# DIO-BNC_Supply.net
KiCad netlist of a schematic drawn in Altium Designer
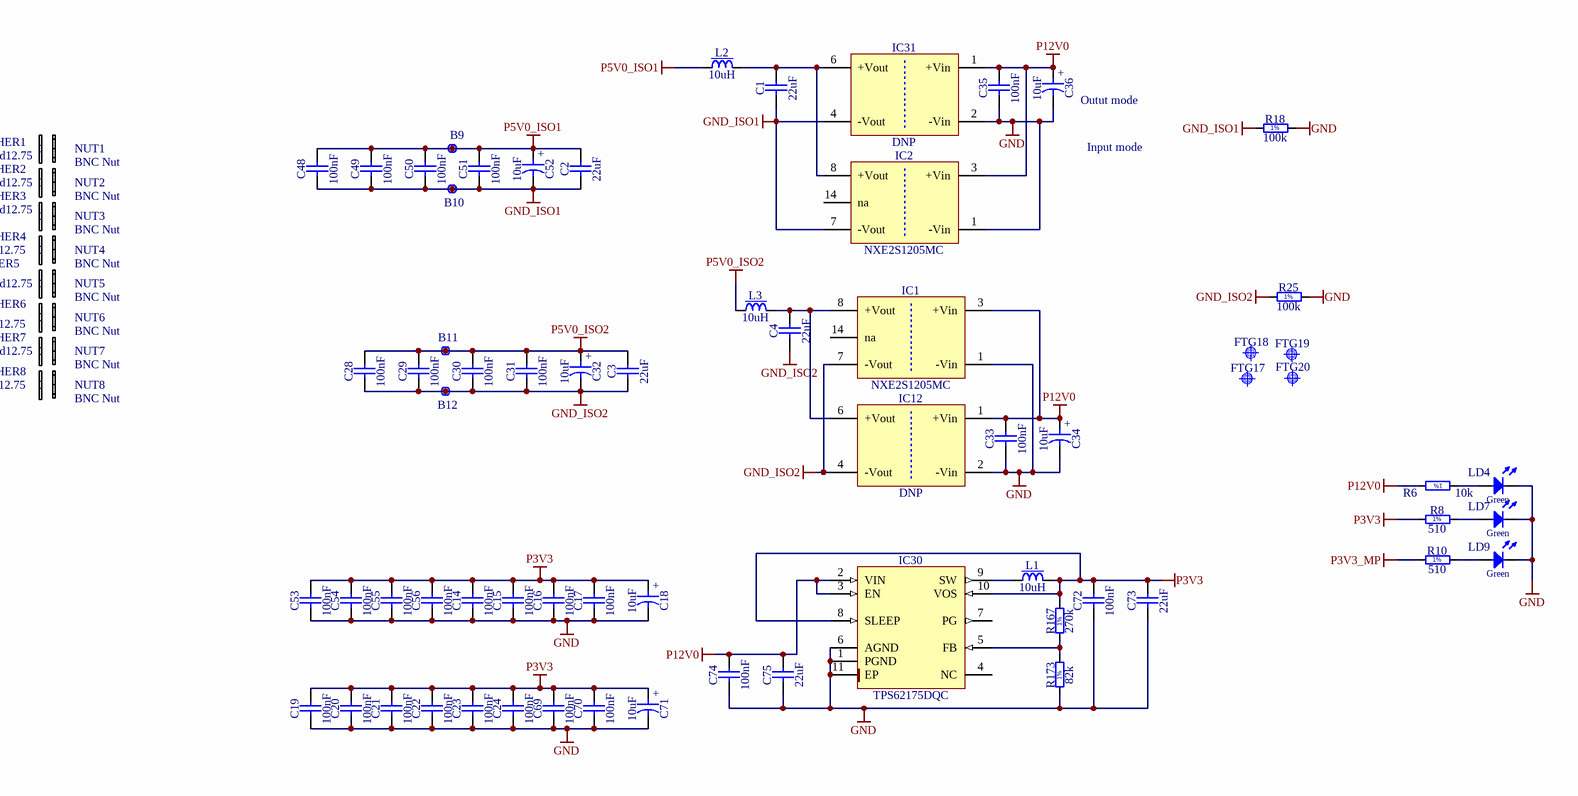
[diagram p0: DIO-BNC_Supply.SchDoc]

(export (version "E")
  (design (tool "Eeschema 10.0.6"))
  (components
    (comp (ref "B9")
      (value "Plated Hole")
      (footprint "c130h60")
      (description "Single Terminal Socket")
      (fields (field (name "PART NUMBER") "PLATED_HOLE0.6_PAD1.3") (field (name "AUTHOR") "CERN DEM MR"))
      (libsource (lib "Eletro-mechanical") (part "Single Terminal Socket"))
    )
    (comp (ref "B10")
      (value "Plated Hole")
      (footprint "c130h60")
      (description "Single Terminal Socket")
      (fields (field (name "PART NUMBER") "PLATED_HOLE0.6_PAD1.3") (field (name "AUTHOR") "CERN DEM MR"))
      (libsource (lib "Eletro-mechanical") (part "Single Terminal Socket"))
    )
    (comp (ref "B11")
      (value "Plated Hole")
      (footprint "c130h60")
      (description "Single Terminal Socket")
      (fields (field (name "PART NUMBER") "PLATED_HOLE0.6_PAD1.3") (field (name "AUTHOR") "CERN DEM MR"))
      (libsource (lib "Eletro-mechanical") (part "Single Terminal Socket"))
    )
    (comp (ref "B12")
      (value "Plated Hole")
      (footprint "c130h60")
      (description "Single Terminal Socket")
      (fields (field (name "PART NUMBER") "PLATED_HOLE0.6_PAD1.3") (field (name "AUTHOR") "CERN DEM MR"))
      (libsource (lib "Eletro-mechanical") (part "Single Terminal Socket"))
    )
    (comp (ref "C1")
      (value "22uF")
      (footprint "CAPC2012X135N")
      (description "Non-polarised capacitor")
      (fields
        (field (name "PART NUMBER") "CC0805_22UF_16V_10%_X5R")
        (field (name "VOLTAGE") "16V")
        (field (name "AUTHOR") "CERN DEM JLC")
      )
      (libsource (lib "Capacitors") (part "Capacitor - non polarized"))
    )
    (comp (ref "C2")
      (value "22uF")
      (footprint "CAPC2012X135N")
      (description "Non-polarised capacitor")
      (fields
        (field (name "PART NUMBER") "CC0805_22UF_16V_10%_X5R")
        (field (name "VOLTAGE") "16V")
        (field (name "AUTHOR") "CERN DEM JLC")
      )
      (libsource (lib "Capacitors") (part "Capacitor - non polarized"))
    )
    (comp (ref "C3")
      (value "22uF")
      (footprint "CAPC2012X135N")
      (description "Non-polarised capacitor")
      (fields
        (field (name "PART NUMBER") "CC0805_22UF_16V_10%_X5R")
        (field (name "VOLTAGE") "16V")
        (field (name "AUTHOR") "CERN DEM JLC")
      )
      (libsource (lib "Capacitors") (part "Capacitor - non polarized"))
    )
    (comp (ref "C4")
      (value "22uF")
      (footprint "CAPC2012X135N")
      (description "Non-polarised capacitor")
      (fields
        (field (name "PART NUMBER") "CC0805_22UF_16V_10%_X5R")
        (field (name "VOLTAGE") "16V")
        (field (name "AUTHOR") "CERN DEM JLC")
      )
      (libsource (lib "Capacitors") (part "Capacitor - non polarized"))
    )
    (comp (ref "C14")
      (value "100nF")
      (footprint "CAPC1005X55N")
      (description "Non-polarised capacitor")
      (fields
        (field (name "PART NUMBER") "CC0402_100NF_16V_10%_X5R")
        (field (name "VOLTAGE") "16V")
        (field (name "AUTHOR") "CERN DEM JLC")
      )
      (libsource (lib "Capacitors") (part "Capacitor - non polarized"))
    )
    (comp (ref "C15")
      (value "100nF")
      (footprint "CAPC1005X55N")
      (description "Non-polarised capacitor")
      (fields
        (field (name "PART NUMBER") "CC0402_100NF_16V_10%_X5R")
        (field (name "VOLTAGE") "16V")
        (field (name "AUTHOR") "CERN DEM JLC")
      )
      (libsource (lib "Capacitors") (part "Capacitor - non polarized"))
    )
    (comp (ref "C16")
      (value "100nF")
      (footprint "CAPC1005X55N")
      (description "Non-polarised capacitor")
      (fields
        (field (name "PART NUMBER") "CC0402_100NF_16V_10%_X5R")
        (field (name "VOLTAGE") "16V")
        (field (name "AUTHOR") "CERN DEM JLC")
      )
      (libsource (lib "Capacitors") (part "Capacitor - non polarized"))
    )
    (comp (ref "C17")
      (value "100nF")
      (footprint "CAPC1005X55N")
      (description "Non-polarised capacitor")
      (fields
        (field (name "PART NUMBER") "CC0402_100NF_16V_10%_X5R")
        (field (name "VOLTAGE") "16V")
        (field (name "AUTHOR") "CERN DEM JLC")
      )
      (libsource (lib "Capacitors") (part "Capacitor - non polarized"))
    )
    (comp (ref "C18")
      (value "10uF")
      (footprint "CAPAE430X540N")
      (description "Polarised capacitor")
      (fields
        (field (name "PART NUMBER") "CAE430-540_10UF_16V_20%")
        (field (name "VOLTAGE") "16V")
        (field (name "AUTHOR") "CERN DEM JLC")
      )
      (libsource (lib "Capacitors") (part "Capacitor - polarized"))
    )
    (comp (ref "C19")
      (value "100nF")
      (footprint "CAPC1005X55N")
      (description "Non-polarised capacitor")
      (fields
        (field (name "PART NUMBER") "CC0402_100NF_16V_10%_X5R")
        (field (name "VOLTAGE") "16V")
        (field (name "AUTHOR") "CERN DEM JLC")
      )
      (libsource (lib "Capacitors") (part "Capacitor - non polarized"))
    )
    (comp (ref "C20")
      (value "100nF")
      (footprint "CAPC1005X55N")
      (description "Non-polarised capacitor")
      (fields
        (field (name "PART NUMBER") "CC0402_100NF_16V_10%_X5R")
        (field (name "VOLTAGE") "16V")
        (field (name "AUTHOR") "CERN DEM JLC")
      )
      (libsource (lib "Capacitors") (part "Capacitor - non polarized"))
    )
    (comp (ref "C21")
      (value "100nF")
      (footprint "CAPC1005X55N")
      (description "Non-polarised capacitor")
      (fields
        (field (name "PART NUMBER") "CC0402_100NF_16V_10%_X5R")
        (field (name "VOLTAGE") "16V")
        (field (name "AUTHOR") "CERN DEM JLC")
      )
      (libsource (lib "Capacitors") (part "Capacitor - non polarized"))
    )
    (comp (ref "C22")
      (value "100nF")
      (footprint "CAPC1005X55N")
      (description "Non-polarised capacitor")
      (fields
        (field (name "PART NUMBER") "CC0402_100NF_16V_10%_X5R")
        (field (name "VOLTAGE") "16V")
        (field (name "AUTHOR") "CERN DEM JLC")
      )
      (libsource (lib "Capacitors") (part "Capacitor - non polarized"))
    )
    (comp (ref "C23")
      (value "100nF")
      (footprint "CAPC1005X55N")
      (description "Non-polarised capacitor")
      (fields
        (field (name "PART NUMBER") "CC0402_100NF_16V_10%_X5R")
        (field (name "VOLTAGE") "16V")
        (field (name "AUTHOR") "CERN DEM JLC")
      )
      (libsource (lib "Capacitors") (part "Capacitor - non polarized"))
    )
    (comp (ref "C24")
      (value "100nF")
      (footprint "CAPC1005X55N")
      (description "Non-polarised capacitor")
      (fields
        (field (name "PART NUMBER") "CC0402_100NF_16V_10%_X5R")
        (field (name "VOLTAGE") "16V")
        (field (name "AUTHOR") "CERN DEM JLC")
      )
      (libsource (lib "Capacitors") (part "Capacitor - non polarized"))
    )
    (comp (ref "C28")
      (value "100nF")
      (footprint "CAPC1005X55N")
      (description "Non-polarised capacitor")
      (fields
        (field (name "PART NUMBER") "CC0402_100NF_16V_10%_X5R")
        (field (name "VOLTAGE") "16V")
        (field (name "AUTHOR") "CERN DEM JLC")
      )
      (libsource (lib "Capacitors") (part "Capacitor - non polarized"))
    )
    (comp (ref "C29")
      (value "100nF")
      (footprint "CAPC1005X55N")
      (description "Non-polarised capacitor")
      (fields
        (field (name "PART NUMBER") "CC0402_100NF_16V_10%_X5R")
        (field (name "VOLTAGE") "16V")
        (field (name "AUTHOR") "CERN DEM JLC")
      )
      (libsource (lib "Capacitors") (part "Capacitor - non polarized"))
    )
    (comp (ref "C30")
      (value "100nF")
      (footprint "CAPC1005X55N")
      (description "Non-polarised capacitor")
      (fields
        (field (name "PART NUMBER") "CC0402_100NF_16V_10%_X5R")
        (field (name "VOLTAGE") "16V")
        (field (name "AUTHOR") "CERN DEM JLC")
      )
      (libsource (lib "Capacitors") (part "Capacitor - non polarized"))
    )
    (comp (ref "C31")
      (value "100nF")
      (footprint "CAPC1005X55N")
      (description "Non-polarised capacitor")
      (fields
        (field (name "PART NUMBER") "CC0402_100NF_16V_10%_X5R")
        (field (name "VOLTAGE") "16V")
        (field (name "AUTHOR") "CERN DEM JLC")
      )
      (libsource (lib "Capacitors") (part "Capacitor - non polarized"))
    )
    (comp (ref "C32")
      (value "10uF")
      (footprint "CAPAE430X540N")
      (description "Polarised capacitor")
      (fields
        (field (name "PART NUMBER") "CAE430-540_10UF_16V_20%")
        (field (name "VOLTAGE") "16V")
        (field (name "AUTHOR") "CERN DEM JLC")
      )
      (libsource (lib "Capacitors") (part "Capacitor - polarized"))
    )
    (comp (ref "C33")
      (value "100nF")
      (footprint "CAPC1005X55N")
      (description "Non-polarised capacitor")
      (fields
        (field (name "PART NUMBER") "CC0402_100NF_16V_10%_X5R")
        (field (name "VOLTAGE") "16V")
        (field (name "AUTHOR") "CERN DEM JLC")
      )
      (libsource (lib "Capacitors") (part "Capacitor - non polarized"))
    )
    (comp (ref "C34")
      (value "10uF")
      (footprint "CAPAE430X540N")
      (description "Polarised capacitor")
      (fields
        (field (name "PART NUMBER") "CAE430-540_10UF_16V_20%")
        (field (name "VOLTAGE") "16V")
        (field (name "AUTHOR") "CERN DEM JLC")
      )
      (libsource (lib "Capacitors") (part "Capacitor - polarized"))
    )
    (comp (ref "C35")
      (value "100nF")
      (footprint "CAPC1005X55N")
      (description "Non-polarised capacitor")
      (fields
        (field (name "PART NUMBER") "CC0402_100NF_16V_10%_X5R")
        (field (name "VOLTAGE") "16V")
        (field (name "AUTHOR") "CERN DEM JLC")
      )
      (libsource (lib "Capacitors") (part "Capacitor - non polarized"))
    )
    (comp (ref "C36")
      (value "10uF")
      (footprint "CAPAE430X540N")
      (description "Polarised capacitor")
      (fields
        (field (name "PART NUMBER") "CAE430-540_10UF_16V_20%")
        (field (name "VOLTAGE") "16V")
        (field (name "AUTHOR") "CERN DEM JLC")
      )
      (libsource (lib "Capacitors") (part "Capacitor - polarized"))
    )
    (comp (ref "C48")
      (value "100nF")
      (footprint "CAPC1005X55N")
      (description "Non-polarised capacitor")
      (fields
        (field (name "PART NUMBER") "CC0402_100NF_16V_10%_X5R")
        (field (name "VOLTAGE") "16V")
        (field (name "AUTHOR") "CERN DEM JLC")
      )
      (libsource (lib "Capacitors") (part "Capacitor - non polarized"))
    )
    (comp (ref "C49")
      (value "100nF")
      (footprint "CAPC1005X55N")
      (description "Non-polarised capacitor")
      (fields
        (field (name "PART NUMBER") "CC0402_100NF_16V_10%_X5R")
        (field (name "VOLTAGE") "16V")
        (field (name "AUTHOR") "CERN DEM JLC")
      )
      (libsource (lib "Capacitors") (part "Capacitor - non polarized"))
    )
    (comp (ref "C50")
      (value "100nF")
      (footprint "CAPC1005X55N")
      (description "Non-polarised capacitor")
      (fields
        (field (name "PART NUMBER") "CC0402_100NF_16V_10%_X5R")
        (field (name "VOLTAGE") "16V")
        (field (name "AUTHOR") "CERN DEM JLC")
      )
      (libsource (lib "Capacitors") (part "Capacitor - non polarized"))
    )
    (comp (ref "C51")
      (value "100nF")
      (footprint "CAPC1005X55N")
      (description "Non-polarised capacitor")
      (fields
        (field (name "PART NUMBER") "CC0402_100NF_16V_10%_X5R")
        (field (name "VOLTAGE") "16V")
        (field (name "AUTHOR") "CERN DEM JLC")
      )
      (libsource (lib "Capacitors") (part "Capacitor - non polarized"))
    )
    (comp (ref "C52")
      (value "10uF")
      (footprint "CAPAE430X540N")
      (description "Polarised capacitor")
      (fields
        (field (name "PART NUMBER") "CAE430-540_10UF_16V_20%")
        (field (name "VOLTAGE") "16V")
        (field (name "AUTHOR") "CERN DEM JLC")
      )
      (libsource (lib "Capacitors") (part "Capacitor - polarized"))
    )
    (comp (ref "C53")
      (value "100nF")
      (footprint "CAPC1005X55N")
      (description "Non-polarised capacitor")
      (fields
        (field (name "PART NUMBER") "CC0402_100NF_16V_10%_X5R")
        (field (name "VOLTAGE") "16V")
        (field (name "AUTHOR") "CERN DEM JLC")
      )
      (libsource (lib "Capacitors") (part "Capacitor - non polarized"))
    )
    (comp (ref "C54")
      (value "100nF")
      (footprint "CAPC1005X55N")
      (description "Non-polarised capacitor")
      (fields
        (field (name "PART NUMBER") "CC0402_100NF_16V_10%_X5R")
        (field (name "VOLTAGE") "16V")
        (field (name "AUTHOR") "CERN DEM JLC")
      )
      (libsource (lib "Capacitors") (part "Capacitor - non polarized"))
    )
    (comp (ref "C55")
      (value "100nF")
      (footprint "CAPC1005X55N")
      (description "Non-polarised capacitor")
      (fields
        (field (name "PART NUMBER") "CC0402_100NF_16V_10%_X5R")
        (field (name "VOLTAGE") "16V")
        (field (name "AUTHOR") "CERN DEM JLC")
      )
      (libsource (lib "Capacitors") (part "Capacitor - non polarized"))
    )
    (comp (ref "C56")
      (value "100nF")
      (footprint "CAPC1005X55N")
      (description "Non-polarised capacitor")
      (fields
        (field (name "PART NUMBER") "CC0402_100NF_16V_10%_X5R")
        (field (name "VOLTAGE") "16V")
        (field (name "AUTHOR") "CERN DEM JLC")
      )
      (libsource (lib "Capacitors") (part "Capacitor - non polarized"))
    )
    (comp (ref "C69")
      (value "100nF")
      (footprint "CAPC1005X55N")
      (description "Non-polarised capacitor")
      (fields
        (field (name "PART NUMBER") "CC0402_100NF_16V_10%_X5R")
        (field (name "VOLTAGE") "16V")
        (field (name "AUTHOR") "CERN DEM JLC")
      )
      (libsource (lib "Capacitors") (part "Capacitor - non polarized"))
    )
    (comp (ref "C70")
      (value "100nF")
      (footprint "CAPC1005X55N")
      (description "Non-polarised capacitor")
      (fields
        (field (name "PART NUMBER") "CC0402_100NF_16V_10%_X5R")
        (field (name "VOLTAGE") "16V")
        (field (name "AUTHOR") "CERN DEM JLC")
      )
      (libsource (lib "Capacitors") (part "Capacitor - non polarized"))
    )
    (comp (ref "C71")
      (value "10uF")
      (footprint "CAPAE430X540N")
      (description "Polarised capacitor")
      (fields
        (field (name "PART NUMBER") "CAE430-540_10UF_16V_20%")
        (field (name "VOLTAGE") "16V")
        (field (name "AUTHOR") "CERN DEM JLC")
      )
      (libsource (lib "Capacitors") (part "Capacitor - polarized"))
    )
    (comp (ref "C72")
      (value "100nF")
      (footprint "CAPC1005X55N")
      (description "Non-polarised capacitor")
      (fields
        (field (name "PART NUMBER") "CC0402_100NF_16V_10%_X5R")
        (field (name "VOLTAGE") "16V")
        (field (name "AUTHOR") "CERN DEM JLC")
      )
      (libsource (lib "Capacitors") (part "Capacitor - non polarized"))
    )
    (comp (ref "C73")
      (value "22uF")
      (footprint "CAPC2012X135N")
      (description "Non-polarised capacitor")
      (fields
        (field (name "PART NUMBER") "CC0805_22UF_16V_10%_X5R")
        (field (name "VOLTAGE") "16V")
        (field (name "AUTHOR") "CERN DEM JLC")
      )
      (libsource (lib "Capacitors") (part "Capacitor - non polarized"))
    )
    (comp (ref "C74")
      (value "100nF")
      (footprint "CAPC1005X55N")
      (description "Non-polarised capacitor")
      (fields
        (field (name "PART NUMBER") "CC0402_100NF_16V_10%_X5R")
        (field (name "VOLTAGE") "16V")
        (field (name "AUTHOR") "CERN DEM JLC")
      )
      (libsource (lib "Capacitors") (part "Capacitor - non polarized"))
    )
    (comp (ref "C75")
      (value "22uF")
      (footprint "CAPC2012X135N")
      (description "Non-polarised capacitor")
      (fields
        (field (name "PART NUMBER") "CC0805_22UF_16V_10%_X5R")
        (field (name "VOLTAGE") "16V")
        (field (name "AUTHOR") "CERN DEM JLC")
      )
      (libsource (lib "Capacitors") (part "Capacitor - non polarized"))
    )
    (comp (ref "FTG17")
      (value "Use only in PCB")
      (footprint "FIDUCIAL_TOP_C100-200")
      (description "Fiducial Target")
      (fields (field (name "PART NUMBER") "FIDUCIAL_TARGET_C100-200") (field (name "AUTHOR") "CERN DEM JLC"))
      (libsource (lib "Eletro-mechanical") (part "Fiducial Target"))
    )
    (comp (ref "FTG18")
      (value "Use only in PCB")
      (footprint "FIDUCIAL_TOP_S100-200")
      (description "Fiducial Target")
      (fields (field (name "PART NUMBER") "FIDUCIAL_TARGET_S100-200") (field (name "AUTHOR") "CERN DEM JLC"))
      (libsource (lib "Eletro-mechanical") (part "Fiducial Target"))
    )
    (comp (ref "FTG19")
      (value "Use only in PCB")
      (footprint "FIDUCIAL_TOP_S200-400")
      (description "Fiducial Target")
      (fields (field (name "PART NUMBER") "FIDUCIAL_TARGET_S200-400") (field (name "AUTHOR") "CERN DEM JLC"))
      (libsource (lib "Eletro-mechanical") (part "Fiducial Target"))
    )
    (comp (ref "FTG20")
      (value "Use only in PCB")
      (footprint "FIDUCIAL_TOP_S100-200")
      (description "Fiducial Target")
      (fields (field (name "PART NUMBER") "FIDUCIAL_TARGET_S100-200") (field (name "AUTHOR") "CERN DEM JLC"))
      (libsource (lib "Eletro-mechanical") (part "Fiducial Target"))
    )
    (comp (ref "IC1")
      (value "NXE2S1205MC")
      (footprint "DCDC_MURATA_NXE2")
      (description "MURATA, NXE2 Serie, Dual Output DCDC Converter")
      (fields (field (name "MANUFACTURER") "MURATA POWER SOLUTIONS") (field (name "AUTHOR") "CERN DEM MR"))
      (libsource (lib "LIBRARY_SCH") (part "DCDC_MURATA_NXE2S1205MC"))
    )
    (comp (ref "IC2")
      (value "NXE2S1205MC")
      (footprint "DCDC_MURATA_NXE2")
      (description "MURATA, NXE2 Serie, Dual Output DCDC Converter")
      (fields (field (name "MANUFACTURER") "MURATA POWER SOLUTIONS") (field (name "AUTHOR") "CERN DEM MR"))
      (libsource (lib "LIBRARY_SCH") (part "DCDC_MURATA_NXE2S1205MC"))
    )
    (comp (ref "IC12")
      (value "DNP")
      (footprint "DCDC_TRACO_TMA")
      (description "1 W Watt, 10.8-13.2VDCVin, 5 V@0.2 A")
      (fields
        (field (name "PART NUMBER") "TMA 1205S")
        (field (name "MANUFACTURER") "TRACO POWER")
        (field (name "AUTHOR") "GK")
      )
      (libsource (lib "LIBRARY_SCH") (part "DC/DC_TRACO_TMA1205S"))
    )
    (comp (ref "IC30")
      (value "TPS62175DQC")
      (footprint "SON50P200X300X80-11N-R94X250")
      (description "4.75-28VDC to 1-6VDC, 500mA Step-Down Converter With Sleep Mode")
      (fields (field (name "MANUFACTURER") "TEXAS INSTRUMENTS") (field (name "AUTHOR") "CERN DEM JMW"))
      (libsource (lib "ICs And Semiconductors") (part "TPS62175"))
    )
    (comp (ref "IC31")
      (value "DNP")
      (footprint "DCDC_TRACO_TMA")
      (description "1 W Watt, 10.8-13.2VDCVin, 5 V@0.2 A")
      (fields
        (field (name "PART NUMBER") "TMA 1205S")
        (field (name "MANUFACTURER") "TRACO POWER")
        (field (name "AUTHOR") "GK")
      )
      (libsource (lib "LIBRARY_SCH") (part "DC/DC_TRACO_TMA1205S"))
    )
    (comp (ref "L1")
      (value "10uH")
      (footprint "IND_MURATA-PS_8400")
      (description "Inductor With Core")
      (fields
        (field (name "PART NUMBER") "IND_10UH_10%_MURATA-PS_8400")
        (field (name "POWER") "950mA")
        (field (name "AUTHOR") "CERN DEM JLC")
      )
      (libsource (lib "Inductors & Transformers") (part "Inductor With Magnetic core"))
    )
    (comp (ref "L2")
      (value "10uH")
      (footprint "IND_MURATA-PS_8400")
      (description "Inductor With Core")
      (fields
        (field (name "PART NUMBER") "IND_10UH_10%_MURATA-PS_8400")
        (field (name "POWER") "950mA")
        (field (name "AUTHOR") "CERN DEM JLC")
      )
      (libsource (lib "Inductors & Transformers") (part "Inductor With Magnetic core"))
    )
    (comp (ref "L3")
      (value "10uH")
      (footprint "IND_MURATA-PS_8400")
      (description "Inductor With Core")
      (fields
        (field (name "PART NUMBER") "IND_10UH_10%_MURATA-PS_8400")
        (field (name "POWER") "950mA")
        (field (name "AUTHOR") "CERN DEM JLC")
      )
      (libsource (lib "Inductors & Transformers") (part "Inductor With Magnetic core"))
    )
    (comp (ref "LD4")
      (value "Green")
      (footprint "LED_KINGBRIGHT_KPH-1608CGCK")
      (description "LED Green 1C 2A")
      (fields
        (field (name "PART NUMBER") "LED_KINGBRIGHT_KPH-1608CGCK")
        (field (name "MANUFACTURER") "KINGBRIGHT")
        (field (name "AUTHOR") "CERN DEM JLC")
      )
      (libsource (lib "ICs And Semiconductors") (part "LED Green 1C 2A"))
    )
    (comp (ref "LD7")
      (value "Green")
      (footprint "LED_KINGBRIGHT_KPH-1608CGCK")
      (description "LED Green 1C 2A")
      (fields
        (field (name "PART NUMBER") "LED_KINGBRIGHT_KPH-1608CGCK")
        (field (name "MANUFACTURER") "KINGBRIGHT")
        (field (name "AUTHOR") "CERN DEM JLC")
      )
      (libsource (lib "ICs And Semiconductors") (part "LED Green 1C 2A"))
    )
    (comp (ref "LD9")
      (value "Green")
      (footprint "LED_KINGBRIGHT_KPH-1608CGCK")
      (description "LED Green 1C 2A")
      (fields
        (field (name "PART NUMBER") "LED_KINGBRIGHT_KPH-1608CGCK")
        (field (name "MANUFACTURER") "KINGBRIGHT")
        (field (name "AUTHOR") "CERN DEM JLC")
      )
      (libsource (lib "ICs And Semiconductors") (part "LED Green 1C 2A"))
    )
    (comp (ref "NUT1")
      (value "BNC Nut")
      (footprint "TE_1-329631-2")
      (description "BNC nut")
      (fields
        (field (name "PART NUMBER") "TE_1-329631-2")
        (field (name "MANUFACTURER") "TE")
        (field (name "AUTHOR") "CERN DEM JLC")
      )
      (libsource (lib "LIBRARY_SCH") (part "MECH_BNC_NUT"))
    )
    (comp (ref "NUT2")
      (value "BNC Nut")
      (footprint "TE_1-329631-2")
      (description "BNC nut")
      (fields
        (field (name "PART NUMBER") "TE_1-329631-2")
        (field (name "MANUFACTURER") "TE")
        (field (name "AUTHOR") "CERN DEM JLC")
      )
      (libsource (lib "LIBRARY_SCH") (part "MECH_BNC_NUT"))
    )
    (comp (ref "NUT3")
      (value "BNC Nut")
      (footprint "TE_1-329631-2")
      (description "BNC nut")
      (fields
        (field (name "PART NUMBER") "TE_1-329631-2")
        (field (name "MANUFACTURER") "TE")
        (field (name "AUTHOR") "CERN DEM JLC")
      )
      (libsource (lib "LIBRARY_SCH") (part "MECH_BNC_NUT"))
    )
    (comp (ref "NUT4")
      (value "BNC Nut")
      (footprint "TE_1-329631-2")
      (description "BNC nut")
      (fields
        (field (name "PART NUMBER") "TE_1-329631-2")
        (field (name "MANUFACTURER") "TE")
        (field (name "AUTHOR") "CERN DEM JLC")
      )
      (libsource (lib "LIBRARY_SCH") (part "MECH_BNC_NUT"))
    )
    (comp (ref "NUT5")
      (value "BNC Nut")
      (footprint "TE_1-329631-2")
      (description "BNC nut")
      (fields
        (field (name "PART NUMBER") "TE_1-329631-2")
        (field (name "MANUFACTURER") "TE")
        (field (name "AUTHOR") "CERN DEM JLC")
      )
      (libsource (lib "LIBRARY_SCH") (part "MECH_BNC_NUT"))
    )
    (comp (ref "NUT6")
      (value "BNC Nut")
      (footprint "TE_1-329631-2")
      (description "BNC nut")
      (fields
        (field (name "PART NUMBER") "TE_1-329631-2")
        (field (name "MANUFACTURER") "TE")
        (field (name "AUTHOR") "CERN DEM JLC")
      )
      (libsource (lib "LIBRARY_SCH") (part "MECH_BNC_NUT"))
    )
    (comp (ref "NUT7")
      (value "BNC Nut")
      (footprint "TE_1-329631-2")
      (description "BNC nut")
      (fields
        (field (name "PART NUMBER") "TE_1-329631-2")
        (field (name "MANUFACTURER") "TE")
        (field (name "AUTHOR") "CERN DEM JLC")
      )
      (libsource (lib "LIBRARY_SCH") (part "MECH_BNC_NUT"))
    )
    (comp (ref "NUT8")
      (value "BNC Nut")
      (footprint "TE_1-329631-2")
      (description "BNC nut")
      (fields
        (field (name "PART NUMBER") "TE_1-329631-2")
        (field (name "MANUFACTURER") "TE")
        (field (name "AUTHOR") "CERN DEM JLC")
      )
      (libsource (lib "LIBRARY_SCH") (part "MECH_BNC_NUT"))
    )
    (comp (ref "R6")
      (value "10k")
      (footprint "RESC1005X40N")
      (description "Resistor - 1%")
      (fields
        (field (name "PART NUMBER") "R0402_10K_1%_0.0625W_100PPM")
        (field (name "POWER") "0.0625W")
        (field (name "AUTHOR") "CERN DEM JLC")
      )
      (libsource (lib "Resistors") (part "Resistor - 1%"))
    )
    (comp (ref "R8")
      (value "510")
      (footprint "RESC1005X40N")
      (description "Resistor - 1%")
      (fields
        (field (name "PART NUMBER") "R0402_510R_1%_0.0625W_100PPM")
        (field (name "POWER") "0.0625W")
        (field (name "AUTHOR") "CERN DEM JLC")
      )
      (libsource (lib "Resistors") (part "Resistor - 1%"))
    )
    (comp (ref "R10")
      (value "510")
      (footprint "RESC1005X40N")
      (description "Resistor - 1%")
      (fields
        (field (name "PART NUMBER") "R0402_510R_1%_0.0625W_100PPM")
        (field (name "POWER") "0.0625W")
        (field (name "AUTHOR") "CERN DEM JLC")
      )
      (libsource (lib "Resistors") (part "Resistor - 1%"))
    )
    (comp (ref "R18")
      (value "100k")
      (footprint "RESC2012X60N")
      (description "Resistor - 1%")
      (fields
        (field (name "PART NUMBER") "R0805_100K_1%_0.125W_100PPM")
        (field (name "POWER") "0.125W")
        (field (name "AUTHOR") "CERN DEM JLC")
      )
      (libsource (lib "Resistors") (part "Resistor - 1%"))
    )
    (comp (ref "R25")
      (value "100k")
      (footprint "RESC2012X60N")
      (description "Resistor - 1%")
      (fields
        (field (name "PART NUMBER") "R0805_100K_1%_0.125W_100PPM")
        (field (name "POWER") "0.125W")
        (field (name "AUTHOR") "CERN DEM JLC")
      )
      (libsource (lib "Resistors") (part "Resistor - 1%"))
    )
    (comp (ref "R167")
      (value "270k")
      (footprint "RESC1608X55N")
      (description "Resistor - 1%")
      (fields
        (field (name "PART NUMBER") "R0603_270K_1%_0.1W_100PPM")
        (field (name "POWER") "0.1W")
        (field (name "AUTHOR") "CERN DEM JLC")
      )
      (libsource (lib "Resistors") (part "Resistor - 1%"))
    )
    (comp (ref "R173")
      (value "82k")
      (footprint "RESC1608X55N")
      (description "Resistor - 1%")
      (fields
        (field (name "PART NUMBER") "R0603_82K_1%_0.1W_100PPM")
        (field (name "POWER") "0.1W")
        (field (name "AUTHOR") "CERN DEM JLC")
      )
      (libsource (lib "Resistors") (part "Resistor - 1%"))
    )
    (comp (ref "WASHER1")
      (value "D15.8d12.75")
      (footprint "TE_1-1634817-0")
      (description "BNC Washer")
      (fields
        (field (name "PART NUMBER") "TE_1-1634817-0")
        (field (name "MANUFACTURER") "TE")
        (field (name "AUTHOR") "GK")
      )
      (libsource (lib "LIBRARY_SCH") (part "MECH_BNC_WASHER"))
    )
    (comp (ref "WASHER2")
      (value "D15.8d12.75")
      (footprint "TE_1-1634817-0")
      (description "BNC Washer")
      (fields
        (field (name "PART NUMBER") "TE_1-1634817-0")
        (field (name "MANUFACTURER") "TE")
        (field (name "AUTHOR") "GK")
      )
      (libsource (lib "LIBRARY_SCH") (part "MECH_BNC_WASHER"))
    )
    (comp (ref "WASHER3")
      (value "D15.8d12.75")
      (footprint "TE_1-1634817-0")
      (description "BNC Washer")
      (fields
        (field (name "PART NUMBER") "TE_1-1634817-0")
        (field (name "MANUFACTURER") "TE")
        (field (name "AUTHOR") "GK")
      )
      (libsource (lib "LIBRARY_SCH") (part "MECH_BNC_WASHER"))
    )
    (comp (ref "WASHER4")
      (value "D15.8d12.75")
      (footprint "TE_1-1634817-0")
      (description "BNC Washer")
      (fields
        (field (name "PART NUMBER") "TE_1-1634817-0")
        (field (name "MANUFACTURER") "TE")
        (field (name "AUTHOR") "GK")
      )
      (libsource (lib "LIBRARY_SCH") (part "MECH_BNC_WASHER"))
    )
    (comp (ref "WASHER5")
      (value "D15.8d12.75")
      (footprint "TE_1-1634817-0")
      (description "BNC Washer")
      (fields
        (field (name "PART NUMBER") "TE_1-1634817-0")
        (field (name "MANUFACTURER") "TE")
        (field (name "AUTHOR") "GK")
      )
      (libsource (lib "LIBRARY_SCH") (part "MECH_BNC_WASHER"))
    )
    (comp (ref "WASHER6")
      (value "D15.8d12.75")
      (footprint "TE_1-1634817-0")
      (description "BNC Washer")
      (fields
        (field (name "PART NUMBER") "TE_1-1634817-0")
        (field (name "MANUFACTURER") "TE")
        (field (name "AUTHOR") "GK")
      )
      (libsource (lib "LIBRARY_SCH") (part "MECH_BNC_WASHER"))
    )
    (comp (ref "WASHER7")
      (value "D15.8d12.75")
      (footprint "TE_1-1634817-0")
      (description "BNC Washer")
      (fields
        (field (name "PART NUMBER") "TE_1-1634817-0")
        (field (name "MANUFACTURER") "TE")
        (field (name "AUTHOR") "GK")
      )
      (libsource (lib "LIBRARY_SCH") (part "MECH_BNC_WASHER"))
    )
    (comp (ref "WASHER8")
      (value "D15.8d12.75")
      (footprint "TE_1-1634817-0")
      (description "BNC Washer")
      (fields
        (field (name "PART NUMBER") "TE_1-1634817-0")
        (field (name "MANUFACTURER") "TE")
        (field (name "AUTHOR") "GK")
      )
      (libsource (lib "LIBRARY_SCH") (part "MECH_BNC_WASHER"))
    )
  )
  (nets
    (net (code "1") (name "GND") (class "Default")
      (node (ref "C14") (pin "1") (pinfunction "1_1") (pintype "passive"))
      (node (ref "C15") (pin "1") (pinfunction "1_1") (pintype "passive"))
      (node (ref "C16") (pin "1") (pinfunction "1_1") (pintype "passive"))
      (node (ref "C17") (pin "1") (pinfunction "1_1") (pintype "passive"))
      (node (ref "C18") (pin "2") (pinfunction "2_2") (pintype "passive"))
      (node (ref "C19") (pin "1") (pinfunction "1_1") (pintype "passive"))
      (node (ref "C20") (pin "1") (pinfunction "1_1") (pintype "passive"))
      (node (ref "C21") (pin "1") (pinfunction "1_1") (pintype "passive"))
      (node (ref "C22") (pin "1") (pinfunction "1_1") (pintype "passive"))
      (node (ref "C23") (pin "1") (pinfunction "1_1") (pintype "passive"))
      (node (ref "C24") (pin "1") (pinfunction "1_1") (pintype "passive"))
      (node (ref "C33") (pin "1") (pinfunction "1_1") (pintype "passive"))
      (node (ref "C34") (pin "2") (pinfunction "2_2") (pintype "passive"))
      (node (ref "C35") (pin "1") (pinfunction "1_1") (pintype "passive"))
      (node (ref "C36") (pin "2") (pinfunction "2_2") (pintype "passive"))
      (node (ref "C53") (pin "1") (pinfunction "1_1") (pintype "passive"))
      (node (ref "C54") (pin "1") (pinfunction "1_1") (pintype "passive"))
      (node (ref "C55") (pin "1") (pinfunction "1_1") (pintype "passive"))
      (node (ref "C56") (pin "1") (pinfunction "1_1") (pintype "passive"))
      (node (ref "C69") (pin "1") (pinfunction "1_1") (pintype "passive"))
      (node (ref "C70") (pin "1") (pinfunction "1_1") (pintype "passive"))
      (node (ref "C71") (pin "2") (pinfunction "2_2") (pintype "passive"))
      (node (ref "C72") (pin "1") (pinfunction "1_1") (pintype "passive"))
      (node (ref "C73") (pin "1") (pinfunction "1_1") (pintype "passive"))
      (node (ref "C74") (pin "1") (pinfunction "1_1") (pintype "passive"))
      (node (ref "C75") (pin "1") (pinfunction "1_1") (pintype "passive"))
      (node (ref "IC1") (pin "1") (pinfunction "-Vin_1") (pintype "power_in"))
      (node (ref "IC12") (pin "2") (pinfunction "-Vin_2") (pintype "power_in"))
      (node (ref "IC2") (pin "1") (pinfunction "-Vin_1") (pintype "power_in"))
      (node (ref "IC30") (pin "1") (pinfunction "PGND_1") (pintype "power_in"))
      (node (ref "IC30") (pin "11") (pinfunction "EP_11") (pintype "power_in"))
      (node (ref "IC30") (pin "6") (pinfunction "AGND_6") (pintype "power_in"))
      (node (ref "IC31") (pin "2") (pinfunction "-Vin_2") (pintype "power_in"))
      (node (ref "LD4") (pin "1") (pinfunction "C_1") (pintype "passive"))
      (node (ref "LD7") (pin "1") (pinfunction "C_1") (pintype "passive"))
      (node (ref "LD9") (pin "1") (pinfunction "C_1") (pintype "passive"))
      (node (ref "R173") (pin "1") (pinfunction "1_1") (pintype "passive"))
      (node (ref "R18") (pin "2") (pinfunction "2_2") (pintype "passive"))
      (node (ref "R25") (pin "2") (pinfunction "2_2") (pintype "passive"))
    )
    (net (code "2") (name "GND_ISO1") (class "Default")
      (node (ref "B10") (pin "1") (pinfunction "1_1") (pintype "bidirectional"))
      (node (ref "C1") (pin "1") (pinfunction "1_1") (pintype "passive"))
      (node (ref "C2") (pin "1") (pinfunction "1_1") (pintype "passive"))
      (node (ref "C48") (pin "1") (pinfunction "1_1") (pintype "passive"))
      (node (ref "C49") (pin "1") (pinfunction "1_1") (pintype "passive"))
      (node (ref "C50") (pin "1") (pinfunction "1_1") (pintype "passive"))
      (node (ref "C51") (pin "1") (pinfunction "1_1") (pintype "passive"))
      (node (ref "C52") (pin "2") (pinfunction "2_2") (pintype "passive"))
      (node (ref "IC2") (pin "7") (pinfunction "-Vout_7") (pintype "power_in"))
      (node (ref "IC31") (pin "4") (pinfunction "-Vout_4") (pintype "power_in"))
      (node (ref "R18") (pin "1") (pinfunction "1_1") (pintype "passive"))
    )
    (net (code "3") (name "GND_ISO2") (class "Default")
      (node (ref "B12") (pin "1") (pinfunction "1_1") (pintype "bidirectional"))
      (node (ref "C28") (pin "1") (pinfunction "1_1") (pintype "passive"))
      (node (ref "C29") (pin "1") (pinfunction "1_1") (pintype "passive"))
      (node (ref "C3") (pin "1") (pinfunction "1_1") (pintype "passive"))
      (node (ref "C30") (pin "1") (pinfunction "1_1") (pintype "passive"))
      (node (ref "C31") (pin "1") (pinfunction "1_1") (pintype "passive"))
      (node (ref "C32") (pin "2") (pinfunction "2_2") (pintype "passive"))
      (node (ref "C4") (pin "1") (pinfunction "1_1") (pintype "passive"))
      (node (ref "IC1") (pin "7") (pinfunction "-Vout_7") (pintype "power_in"))
      (node (ref "IC12") (pin "4") (pinfunction "-Vout_4") (pintype "power_in"))
      (node (ref "R25") (pin "1") (pinfunction "1_1") (pintype "passive"))
    )
    (net (code "4") (name "Net-(IC1-+Vout)") (class "Default")
      (node (ref "C4") (pin "2") (pinfunction "2_2") (pintype "passive"))
      (node (ref "IC1") (pin "8") (pinfunction "+Vout_8") (pintype "power_in"))
      (node (ref "IC12") (pin "6") (pinfunction "+Vout_6") (pintype "power_in"))
      (node (ref "L3") (pin "2") (pinfunction "2_2") (pintype "passive"))
    )
    (net (code "5") (name "Net-(IC2-+Vout)") (class "Default")
      (node (ref "C1") (pin "2") (pinfunction "2_2") (pintype "passive"))
      (node (ref "IC2") (pin "8") (pinfunction "+Vout_8") (pintype "power_in"))
      (node (ref "IC31") (pin "6") (pinfunction "+Vout_6") (pintype "power_in"))
      (node (ref "L2") (pin "2") (pinfunction "2_2") (pintype "passive"))
    )
    (net (code "6") (name "Net-(IC30-FB)") (class "Default")
      (node (ref "IC30") (pin "5") (pinfunction "FB_5") (pintype "input"))
      (node (ref "R167") (pin "1") (pinfunction "1_1") (pintype "passive"))
      (node (ref "R173") (pin "2") (pinfunction "2_2") (pintype "passive"))
    )
    (net (code "7") (name "Net-(IC30-SW)") (class "Default")
      (node (ref "IC30") (pin "9") (pinfunction "SW_9") (pintype "output"))
      (node (ref "L1") (pin "1") (pinfunction "1_1") (pintype "passive"))
    )
    (net (code "8") (name "Net-(LD4-A)") (class "Default")
      (node (ref "LD4") (pin "2") (pinfunction "A_2") (pintype "passive"))
      (node (ref "R6") (pin "1") (pinfunction "1_1") (pintype "passive"))
    )
    (net (code "9") (name "Net-(LD7-A)") (class "Default")
      (node (ref "LD7") (pin "2") (pinfunction "A_2") (pintype "passive"))
      (node (ref "R8") (pin "2") (pinfunction "2_2") (pintype "passive"))
    )
    (net (code "10") (name "Net-(LD9-A)") (class "Default")
      (node (ref "LD9") (pin "2") (pinfunction "A_2") (pintype "passive"))
      (node (ref "R10") (pin "2") (pinfunction "2_2") (pintype "passive"))
    )
    (net (code "11") (name "P3V3") (class "Default")
      (node (ref "C14") (pin "2") (pinfunction "2_2") (pintype "passive"))
      (node (ref "C15") (pin "2") (pinfunction "2_2") (pintype "passive"))
      (node (ref "C16") (pin "2") (pinfunction "2_2") (pintype "passive"))
      (node (ref "C17") (pin "2") (pinfunction "2_2") (pintype "passive"))
      (node (ref "C18") (pin "1") (pinfunction "1_1") (pintype "passive"))
      (node (ref "C19") (pin "2") (pinfunction "2_2") (pintype "passive"))
      (node (ref "C20") (pin "2") (pinfunction "2_2") (pintype "passive"))
      (node (ref "C21") (pin "2") (pinfunction "2_2") (pintype "passive"))
      (node (ref "C22") (pin "2") (pinfunction "2_2") (pintype "passive"))
      (node (ref "C23") (pin "2") (pinfunction "2_2") (pintype "passive"))
      (node (ref "C24") (pin "2") (pinfunction "2_2") (pintype "passive"))
      (node (ref "C53") (pin "2") (pinfunction "2_2") (pintype "passive"))
      (node (ref "C54") (pin "2") (pinfunction "2_2") (pintype "passive"))
      (node (ref "C55") (pin "2") (pinfunction "2_2") (pintype "passive"))
      (node (ref "C56") (pin "2") (pinfunction "2_2") (pintype "passive"))
      (node (ref "C69") (pin "2") (pinfunction "2_2") (pintype "passive"))
      (node (ref "C70") (pin "2") (pinfunction "2_2") (pintype "passive"))
      (node (ref "C71") (pin "1") (pinfunction "1_1") (pintype "passive"))
      (node (ref "C72") (pin "2") (pinfunction "2_2") (pintype "passive"))
      (node (ref "C73") (pin "2") (pinfunction "2_2") (pintype "passive"))
      (node (ref "IC30") (pin "10") (pinfunction "VOS_10") (pintype "input"))
      (node (ref "IC30") (pin "8") (pinfunction "SLEEP_8") (pintype "input"))
      (node (ref "L1") (pin "2") (pinfunction "2_2") (pintype "passive"))
      (node (ref "R167") (pin "2") (pinfunction "2_2") (pintype "passive"))
      (node (ref "R8") (pin "1") (pinfunction "1_1") (pintype "passive"))
    )
    (net (code "12") (name "P3V3_MP") (class "Default")
      (node (ref "R10") (pin "1") (pinfunction "1_1") (pintype "passive"))
    )
    (net (code "13") (name "P5V0_ISO1") (class "Default")
      (node (ref "B9") (pin "1") (pinfunction "1_1") (pintype "bidirectional"))
      (node (ref "C2") (pin "2") (pinfunction "2_2") (pintype "passive"))
      (node (ref "C48") (pin "2") (pinfunction "2_2") (pintype "passive"))
      (node (ref "C49") (pin "2") (pinfunction "2_2") (pintype "passive"))
      (node (ref "C50") (pin "2") (pinfunction "2_2") (pintype "passive"))
      (node (ref "C51") (pin "2") (pinfunction "2_2") (pintype "passive"))
      (node (ref "C52") (pin "1") (pinfunction "1_1") (pintype "passive"))
      (node (ref "L2") (pin "1") (pinfunction "1_1") (pintype "passive"))
    )
    (net (code "14") (name "P5V0_ISO2") (class "Default")
      (node (ref "B11") (pin "1") (pinfunction "1_1") (pintype "bidirectional"))
      (node (ref "C28") (pin "2") (pinfunction "2_2") (pintype "passive"))
      (node (ref "C29") (pin "2") (pinfunction "2_2") (pintype "passive"))
      (node (ref "C3") (pin "2") (pinfunction "2_2") (pintype "passive"))
      (node (ref "C30") (pin "2") (pinfunction "2_2") (pintype "passive"))
      (node (ref "C31") (pin "2") (pinfunction "2_2") (pintype "passive"))
      (node (ref "C32") (pin "1") (pinfunction "1_1") (pintype "passive"))
      (node (ref "L3") (pin "1") (pinfunction "1_1") (pintype "passive"))
    )
    (net (code "15") (name "P12V0") (class "Default")
      (node (ref "C33") (pin "2") (pinfunction "2_2") (pintype "passive"))
      (node (ref "C34") (pin "1") (pinfunction "1_1") (pintype "passive"))
      (node (ref "C35") (pin "2") (pinfunction "2_2") (pintype "passive"))
      (node (ref "C36") (pin "1") (pinfunction "1_1") (pintype "passive"))
      (node (ref "C74") (pin "2") (pinfunction "2_2") (pintype "passive"))
      (node (ref "C75") (pin "2") (pinfunction "2_2") (pintype "passive"))
      (node (ref "IC1") (pin "3") (pinfunction "+Vin_3") (pintype "power_in"))
      (node (ref "IC12") (pin "1") (pinfunction "+Vin_1") (pintype "power_in"))
      (node (ref "IC2") (pin "3") (pinfunction "+Vin_3") (pintype "power_in"))
      (node (ref "IC30") (pin "2") (pinfunction "VIN_2") (pintype "input"))
      (node (ref "IC30") (pin "3") (pinfunction "EN_3") (pintype "input"))
      (node (ref "IC31") (pin "1") (pinfunction "+Vin_1") (pintype "power_in"))
      (node (ref "R6") (pin "2") (pinfunction "2_2") (pintype "passive"))
    )
    (net (code "16") (name "unconnected-(IC1-na-Pad14)") (class "Default")
      (node (ref "IC1") (pin "14") (pinfunction "na_14") (pintype "passive"))
    )
    (net (code "17") (name "unconnected-(IC2-na-Pad14)") (class "Default")
      (node (ref "IC2") (pin "14") (pinfunction "na_14") (pintype "passive"))
    )
    (net (code "18") (name "unconnected-(IC30-NC-Pad4)") (class "Default")
      (node (ref "IC30") (pin "4") (pinfunction "NC_4") (pintype "passive"))
    )
    (net (code "19") (name "unconnected-(IC30-PG-Pad7)") (class "Default")
      (node (ref "IC30") (pin "7") (pinfunction "PG_7") (pintype "output"))
    )
  )
)
